# Crossing_v1_0.net
KiCad netlist of a schematic drawn in EAGLE
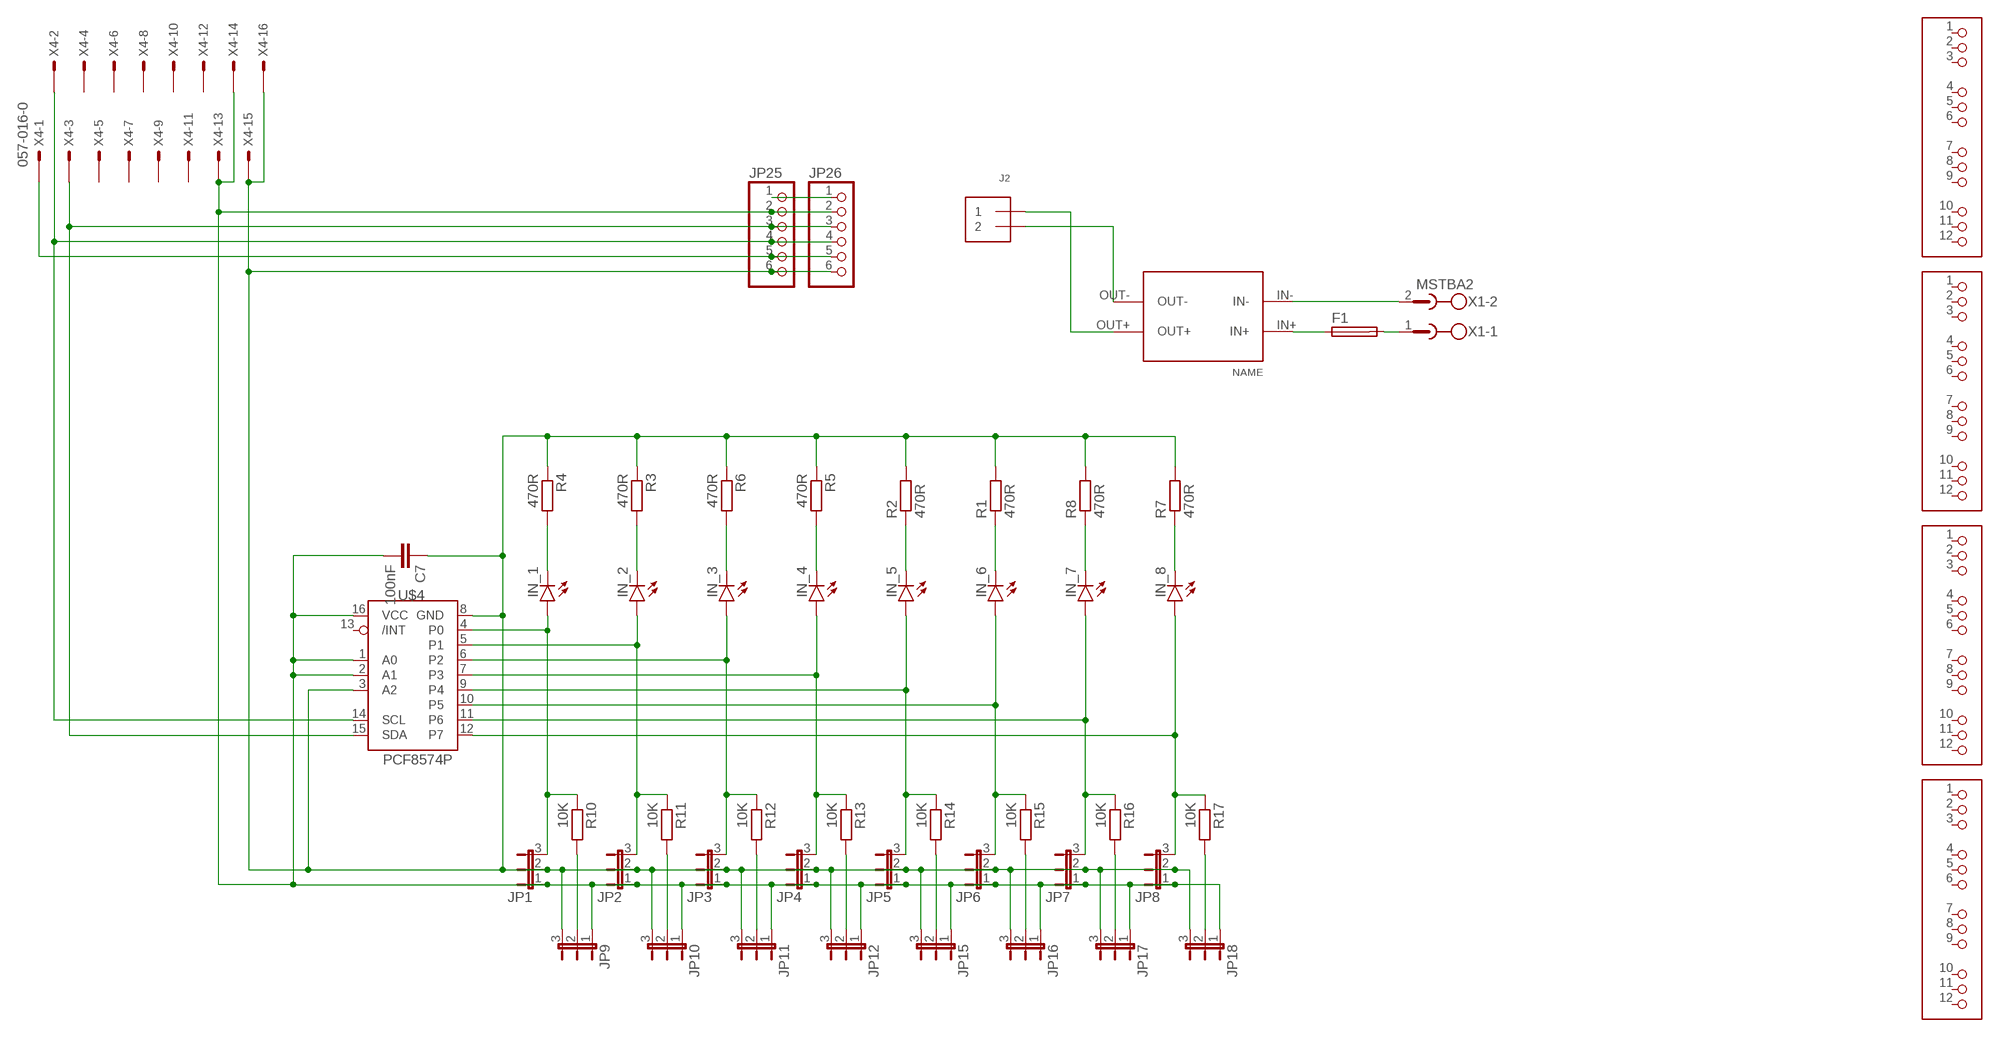
[diagram p0: schematic, sheet 1]

(export (version "E")
  (design (tool "Eeschema 10.0.6"))
  (components
    (comp (ref "C7")
      (value "100nF")
      (footprint "eagle-import:C025-024X044")
      (libsource (lib "eagle-import") (part "C-EU025-024X044"))
    )
    (comp (ref "F1")
      (value "SH25")
      (footprint "eagle-import:SH25")
      (fields (field (name "MF") "SCHURTER") (field (name "MPN") "0031.8211"))
      (libsource (lib "eagle-import") (part "SH25"))
    )
    (comp (ref "IN_1")
      (value "LED3MM")
      (footprint "eagle-import:LED3MM")
      (libsource (lib "eagle-import") (part "LED3MM"))
    )
    (comp (ref "IN_2")
      (value "LED3MM")
      (footprint "eagle-import:LED3MM")
      (libsource (lib "eagle-import") (part "LED3MM"))
    )
    (comp (ref "IN_3")
      (value "LED3MM")
      (footprint "eagle-import:LED3MM")
      (libsource (lib "eagle-import") (part "LED3MM"))
    )
    (comp (ref "IN_4")
      (value "LED3MM")
      (footprint "eagle-import:LED3MM")
      (libsource (lib "eagle-import") (part "LED3MM"))
    )
    (comp (ref "IN_5")
      (value "LED3MM")
      (footprint "eagle-import:LED3MM")
      (libsource (lib "eagle-import") (part "LED3MM"))
    )
    (comp (ref "IN_6")
      (value "LED3MM")
      (footprint "eagle-import:LED3MM")
      (libsource (lib "eagle-import") (part "LED3MM"))
    )
    (comp (ref "IN_7")
      (value "LED3MM")
      (footprint "eagle-import:LED3MM")
      (libsource (lib "eagle-import") (part "LED3MM"))
    )
    (comp (ref "IN_8")
      (value "LED3MM")
      (footprint "eagle-import:LED3MM")
      (libsource (lib "eagle-import") (part "LED3MM"))
    )
    (comp (ref "J2")
      (value "TERMBLOCK_1X2")
      (footprint "eagle-import:TERMBLOCK_1X2-3.5MM")
      (libsource (lib "eagle-import") (part "TERMBLOCK_1X2"))
    )
    (comp (ref "JP1")
      (value "JP2E")
      (footprint "eagle-import:JP2")
      (libsource (lib "eagle-import") (part "JP2E"))
    )
    (comp (ref "JP2")
      (value "JP2E")
      (footprint "eagle-import:JP2")
      (libsource (lib "eagle-import") (part "JP2E"))
    )
    (comp (ref "JP3")
      (value "JP2E")
      (footprint "eagle-import:JP2")
      (libsource (lib "eagle-import") (part "JP2E"))
    )
    (comp (ref "JP4")
      (value "JP2E")
      (footprint "eagle-import:JP2")
      (libsource (lib "eagle-import") (part "JP2E"))
    )
    (comp (ref "JP5")
      (value "JP2E")
      (footprint "eagle-import:JP2")
      (libsource (lib "eagle-import") (part "JP2E"))
    )
    (comp (ref "JP6")
      (value "JP2E")
      (footprint "eagle-import:JP2")
      (libsource (lib "eagle-import") (part "JP2E"))
    )
    (comp (ref "JP7")
      (value "JP2E")
      (footprint "eagle-import:JP2")
      (libsource (lib "eagle-import") (part "JP2E"))
    )
    (comp (ref "JP8")
      (value "JP2E")
      (footprint "eagle-import:JP2")
      (libsource (lib "eagle-import") (part "JP2E"))
    )
    (comp (ref "JP9")
      (value "JP2E")
      (footprint "eagle-import:JP2")
      (libsource (lib "eagle-import") (part "JP2E"))
    )
    (comp (ref "JP10")
      (value "JP2E")
      (footprint "eagle-import:JP2")
      (libsource (lib "eagle-import") (part "JP2E"))
    )
    (comp (ref "JP11")
      (value "JP2E")
      (footprint "eagle-import:JP2")
      (libsource (lib "eagle-import") (part "JP2E"))
    )
    (comp (ref "JP12")
      (value "JP2E")
      (footprint "eagle-import:JP2")
      (libsource (lib "eagle-import") (part "JP2E"))
    )
    (comp (ref "JP15")
      (value "JP2E")
      (footprint "eagle-import:JP2")
      (libsource (lib "eagle-import") (part "JP2E"))
    )
    (comp (ref "JP16")
      (value "JP2E")
      (footprint "eagle-import:JP2")
      (libsource (lib "eagle-import") (part "JP2E"))
    )
    (comp (ref "JP17")
      (value "JP2E")
      (footprint "eagle-import:JP2")
      (libsource (lib "eagle-import") (part "JP2E"))
    )
    (comp (ref "JP18")
      (value "JP2E")
      (footprint "eagle-import:JP2")
      (libsource (lib "eagle-import") (part "JP2E"))
    )
    (comp (ref "JP25")
      (value "PINHD-1X6CB")
      (footprint "eagle-import:1X06-CLEANBIG")
      (libsource (lib "eagle-import") (part "PINHD-1X6CB"))
    )
    (comp (ref "JP26")
      (value "PINHD-1X6CB")
      (footprint "eagle-import:1X06-CLEANBIG")
      (libsource (lib "eagle-import") (part "PINHD-1X6CB"))
    )
    (comp (ref "JP27")
      (value "HEADER-3X04")
      (footprint "eagle-import:3X04")
      (libsource (lib "eagle-import") (part "HEADER-3X04"))
    )
    (comp (ref "JP28")
      (value "HEADER-3X04")
      (footprint "eagle-import:3X04")
      (libsource (lib "eagle-import") (part "HEADER-3X04"))
    )
    (comp (ref "JP29")
      (value "HEADER-3X04")
      (footprint "eagle-import:3X04")
      (libsource (lib "eagle-import") (part "HEADER-3X04"))
    )
    (comp (ref "JP30")
      (value "HEADER-3X04")
      (footprint "eagle-import:3X04")
      (libsource (lib "eagle-import") (part "HEADER-3X04"))
    )
    (comp (ref "R1")
      (value "470R")
      (footprint "eagle-import:0309_10")
      (libsource (lib "eagle-import") (part "R-EU_0309/10"))
    )
    (comp (ref "R2")
      (value "470R")
      (footprint "eagle-import:0309_10")
      (libsource (lib "eagle-import") (part "R-EU_0309/10"))
    )
    (comp (ref "R3")
      (value "470R")
      (footprint "eagle-import:0309_10")
      (libsource (lib "eagle-import") (part "R-EU_0309/10"))
    )
    (comp (ref "R4")
      (value "470R")
      (footprint "eagle-import:0309_10")
      (libsource (lib "eagle-import") (part "R-EU_0309/10"))
    )
    (comp (ref "R5")
      (value "470R")
      (footprint "eagle-import:0309_10")
      (libsource (lib "eagle-import") (part "R-EU_0309/10"))
    )
    (comp (ref "R6")
      (value "470R")
      (footprint "eagle-import:0309_10")
      (libsource (lib "eagle-import") (part "R-EU_0309/10"))
    )
    (comp (ref "R7")
      (value "470R")
      (footprint "eagle-import:0309_10")
      (libsource (lib "eagle-import") (part "R-EU_0309/10"))
    )
    (comp (ref "R8")
      (value "470R")
      (footprint "eagle-import:0309_10")
      (libsource (lib "eagle-import") (part "R-EU_0309/10"))
    )
    (comp (ref "R10")
      (value "10K")
      (footprint "eagle-import:0309_10")
      (libsource (lib "eagle-import") (part "R-EU_0309/10"))
    )
    (comp (ref "R11")
      (value "10K")
      (footprint "eagle-import:0309_10")
      (libsource (lib "eagle-import") (part "R-EU_0309/10"))
    )
    (comp (ref "R12")
      (value "10K")
      (footprint "eagle-import:0309_10")
      (libsource (lib "eagle-import") (part "R-EU_0309/10"))
    )
    (comp (ref "R13")
      (value "10K")
      (footprint "eagle-import:0309_10")
      (libsource (lib "eagle-import") (part "R-EU_0309/10"))
    )
    (comp (ref "R14")
      (value "10K")
      (footprint "eagle-import:0309_10")
      (libsource (lib "eagle-import") (part "R-EU_0309/10"))
    )
    (comp (ref "R15")
      (value "10K")
      (footprint "eagle-import:0309_10")
      (libsource (lib "eagle-import") (part "R-EU_0309/10"))
    )
    (comp (ref "R16")
      (value "10K")
      (footprint "eagle-import:0309_10")
      (libsource (lib "eagle-import") (part "R-EU_0309/10"))
    )
    (comp (ref "R17")
      (value "10K")
      (footprint "eagle-import:0309_10")
      (libsource (lib "eagle-import") (part "R-EU_0309/10"))
    )
    (comp (ref "U$2")
      (value "CP8-ADJ")
      (footprint "eagle-import:CP8-ADJ")
      (libsource (lib "eagle-import") (part "CP8-ADJ"))
    )
    (comp (ref "U$4")
      (value "PCF8574P")
      (footprint "eagle-import:DIL16")
      (libsource (lib "eagle-import") (part "PCF8574P"))
    )
    (comp (ref "X1")
      (value "MSTBA2")
      (footprint "eagle-import:MSTBA2")
      (fields (field (name "MF") "FARNELL") (field (name "MPN") "1757242"))
      (libsource (lib "eagle-import") (part "MSTBA2"))
    )
    (comp (ref "X4")
      (value "057-016-0")
      (footprint "eagle-import:057-016-0")
      (libsource (lib "eagle-import") (part "057-016-0"))
    )
  )
  (nets
    (net (code "1") (name "Net-(F1-Pad1)") (class "Default")
      (node (ref "F1") (pin "1") (pinfunction "1_1") (pintype "passive"))
      (node (ref "U$2") (pin "IN+") (pinfunction "IN+_IN+") (pintype "passive"))
    )
    (net (code "2") (name "Net-(F1-Pad2)") (class "Default")
      (node (ref "F1") (pin "2") (pinfunction "2_2") (pintype "passive"))
      (node (ref "X1") (pin "1") (pinfunction "1_1") (pintype "passive"))
    )
    (net (code "3") (name "Net-(IN_1-C)") (class "Default")
      (node (ref "IN_1") (pin "K") (pinfunction "C_K") (pintype "passive"))
      (node (ref "R4") (pin "2") (pinfunction "2_2") (pintype "passive"))
    )
    (net (code "4") (name "Net-(IN_2-C)") (class "Default")
      (node (ref "IN_2") (pin "K") (pinfunction "C_K") (pintype "passive"))
      (node (ref "R3") (pin "2") (pinfunction "2_2") (pintype "passive"))
    )
    (net (code "5") (name "Net-(IN_3-C)") (class "Default")
      (node (ref "IN_3") (pin "K") (pinfunction "C_K") (pintype "passive"))
      (node (ref "R6") (pin "2") (pinfunction "2_2") (pintype "passive"))
    )
    (net (code "6") (name "Net-(IN_4-C)") (class "Default")
      (node (ref "IN_4") (pin "K") (pinfunction "C_K") (pintype "passive"))
      (node (ref "R5") (pin "2") (pinfunction "2_2") (pintype "passive"))
    )
    (net (code "7") (name "Net-(IN_5-C)") (class "Default")
      (node (ref "IN_5") (pin "K") (pinfunction "C_K") (pintype "passive"))
      (node (ref "R2") (pin "1") (pinfunction "1_1") (pintype "passive"))
    )
    (net (code "8") (name "Net-(IN_6-C)") (class "Default")
      (node (ref "IN_6") (pin "K") (pinfunction "C_K") (pintype "passive"))
      (node (ref "R1") (pin "1") (pinfunction "1_1") (pintype "passive"))
    )
    (net (code "9") (name "Net-(IN_7-C)") (class "Default")
      (node (ref "IN_7") (pin "K") (pinfunction "C_K") (pintype "passive"))
      (node (ref "R8") (pin "1") (pinfunction "1_1") (pintype "passive"))
    )
    (net (code "10") (name "Net-(IN_8-C)") (class "Default")
      (node (ref "IN_8") (pin "K") (pinfunction "C_K") (pintype "passive"))
      (node (ref "R7") (pin "1") (pinfunction "1_1") (pintype "passive"))
    )
    (net (code "11") (name "Net-(J2-Pad1)") (class "Default")
      (node (ref "J2") (pin "1") (pinfunction "1_1") (pintype "passive"))
      (node (ref "U$2") (pin "OUT+") (pinfunction "OUT+_OUT+") (pintype "passive"))
    )
    (net (code "12") (name "Net-(J2-Pad2)") (class "Default")
      (node (ref "J2") (pin "2") (pinfunction "2_2") (pintype "passive"))
      (node (ref "U$2") (pin "OUT-") (pinfunction "OUT-_OUT-") (pintype "passive"))
    )
    (net (code "13") (name "Net-(JP9-Pad2)") (class "Default")
      (node (ref "JP9") (pin "2") (pinfunction "2_2") (pintype "passive"))
      (node (ref "R10") (pin "2") (pinfunction "2_2") (pintype "passive"))
    )
    (net (code "14") (name "Net-(JP10-Pad2)") (class "Default")
      (node (ref "JP10") (pin "2") (pinfunction "2_2") (pintype "passive"))
      (node (ref "R11") (pin "2") (pinfunction "2_2") (pintype "passive"))
    )
    (net (code "15") (name "Net-(JP11-Pad2)") (class "Default")
      (node (ref "JP11") (pin "2") (pinfunction "2_2") (pintype "passive"))
      (node (ref "R12") (pin "2") (pinfunction "2_2") (pintype "passive"))
    )
    (net (code "16") (name "Net-(JP12-Pad2)") (class "Default")
      (node (ref "JP12") (pin "2") (pinfunction "2_2") (pintype "passive"))
      (node (ref "R13") (pin "2") (pinfunction "2_2") (pintype "passive"))
    )
    (net (code "17") (name "Net-(JP15-Pad2)") (class "Default")
      (node (ref "JP15") (pin "2") (pinfunction "2_2") (pintype "passive"))
      (node (ref "R14") (pin "2") (pinfunction "2_2") (pintype "passive"))
    )
    (net (code "18") (name "Net-(JP16-Pad2)") (class "Default")
      (node (ref "JP16") (pin "2") (pinfunction "2_2") (pintype "passive"))
      (node (ref "R15") (pin "2") (pinfunction "2_2") (pintype "passive"))
    )
    (net (code "19") (name "Net-(JP17-Pad2)") (class "Default")
      (node (ref "JP17") (pin "2") (pinfunction "2_2") (pintype "passive"))
      (node (ref "R16") (pin "2") (pinfunction "2_2") (pintype "passive"))
    )
    (net (code "20") (name "Net-(JP18-Pad2)") (class "Default")
      (node (ref "JP18") (pin "2") (pinfunction "2_2") (pintype "passive"))
      (node (ref "R17") (pin "2") (pinfunction "2_2") (pintype "passive"))
    )
    (net (code "21") (name "Net-(JP25-Pad1)") (class "Default")
      (node (ref "JP25") (pin "1") (pinfunction "1_1") (pintype "passive"))
      (node (ref "JP26") (pin "1") (pinfunction "1_1") (pintype "passive"))
    )
    (net (code "22") (name "Net-(U$4-A0)") (class "Default")
      (node (ref "C7") (pin "2") (pinfunction "2_2") (pintype "passive"))
      (node (ref "JP1") (pin "1") (pinfunction "1_1") (pintype "passive"))
      (node (ref "JP10") (pin "1") (pinfunction "1_1") (pintype "passive"))
      (node (ref "JP11") (pin "1") (pinfunction "1_1") (pintype "passive"))
      (node (ref "JP12") (pin "1") (pinfunction "1_1") (pintype "passive"))
      (node (ref "JP15") (pin "1") (pinfunction "1_1") (pintype "passive"))
      (node (ref "JP16") (pin "1") (pinfunction "1_1") (pintype "passive"))
      (node (ref "JP17") (pin "1") (pinfunction "1_1") (pintype "passive"))
      (node (ref "JP18") (pin "1") (pinfunction "1_1") (pintype "passive"))
      (node (ref "JP2") (pin "1") (pinfunction "1_1") (pintype "passive"))
      (node (ref "JP25") (pin "2") (pinfunction "2_2") (pintype "passive"))
      (node (ref "JP26") (pin "2") (pinfunction "2_2") (pintype "passive"))
      (node (ref "JP3") (pin "1") (pinfunction "1_1") (pintype "passive"))
      (node (ref "JP4") (pin "1") (pinfunction "1_1") (pintype "passive"))
      (node (ref "JP5") (pin "1") (pinfunction "1_1") (pintype "passive"))
      (node (ref "JP6") (pin "1") (pinfunction "1_1") (pintype "passive"))
      (node (ref "JP7") (pin "1") (pinfunction "1_1") (pintype "passive"))
      (node (ref "JP8") (pin "1") (pinfunction "1_1") (pintype "passive"))
      (node (ref "JP9") (pin "1") (pinfunction "1_1") (pintype "passive"))
      (node (ref "U$4") (pin "1") (pinfunction "A0_1") (pintype "input"))
      (node (ref "U$4") (pin "16") (pinfunction "VCC_16") (pintype "power_in"))
      (node (ref "U$4") (pin "2") (pinfunction "A1_2") (pintype "input"))
      (node (ref "X4") (pin "13") (pinfunction "S_13") (pintype "passive"))
      (node (ref "X4") (pin "14") (pinfunction "S_14") (pintype "passive"))
    )
    (net (code "23") (name "Net-(U$4-A2)") (class "Default")
      (node (ref "C7") (pin "1") (pinfunction "1_1") (pintype "passive"))
      (node (ref "JP1") (pin "2") (pinfunction "2_2") (pintype "passive"))
      (node (ref "JP10") (pin "3") (pinfunction "3_3") (pintype "passive"))
      (node (ref "JP11") (pin "3") (pinfunction "3_3") (pintype "passive"))
      (node (ref "JP12") (pin "3") (pinfunction "3_3") (pintype "passive"))
      (node (ref "JP15") (pin "3") (pinfunction "3_3") (pintype "passive"))
      (node (ref "JP16") (pin "3") (pinfunction "3_3") (pintype "passive"))
      (node (ref "JP17") (pin "3") (pinfunction "3_3") (pintype "passive"))
      (node (ref "JP18") (pin "3") (pinfunction "3_3") (pintype "passive"))
      (node (ref "JP2") (pin "2") (pinfunction "2_2") (pintype "passive"))
      (node (ref "JP25") (pin "6") (pinfunction "6_6") (pintype "passive"))
      (node (ref "JP26") (pin "6") (pinfunction "6_6") (pintype "passive"))
      (node (ref "JP3") (pin "2") (pinfunction "2_2") (pintype "passive"))
      (node (ref "JP4") (pin "2") (pinfunction "2_2") (pintype "passive"))
      (node (ref "JP5") (pin "2") (pinfunction "2_2") (pintype "passive"))
      (node (ref "JP6") (pin "2") (pinfunction "2_2") (pintype "passive"))
      (node (ref "JP7") (pin "2") (pinfunction "2_2") (pintype "passive"))
      (node (ref "JP8") (pin "2") (pinfunction "2_2") (pintype "passive"))
      (node (ref "JP9") (pin "3") (pinfunction "3_3") (pintype "passive"))
      (node (ref "R1") (pin "2") (pinfunction "2_2") (pintype "passive"))
      (node (ref "R2") (pin "2") (pinfunction "2_2") (pintype "passive"))
      (node (ref "R3") (pin "1") (pinfunction "1_1") (pintype "passive"))
      (node (ref "R4") (pin "1") (pinfunction "1_1") (pintype "passive"))
      (node (ref "R5") (pin "1") (pinfunction "1_1") (pintype "passive"))
      (node (ref "R6") (pin "1") (pinfunction "1_1") (pintype "passive"))
      (node (ref "R7") (pin "2") (pinfunction "2_2") (pintype "passive"))
      (node (ref "R8") (pin "2") (pinfunction "2_2") (pintype "passive"))
      (node (ref "U$4") (pin "3") (pinfunction "A2_3") (pintype "input"))
      (node (ref "U$4") (pin "8") (pinfunction "GND_8") (pintype "power_in"))
      (node (ref "X4") (pin "15") (pinfunction "S_15") (pintype "passive"))
      (node (ref "X4") (pin "16") (pinfunction "S_16") (pintype "passive"))
    )
    (net (code "24") (name "Net-(U$4-P0)") (class "Default")
      (node (ref "IN_1") (pin "A") (pinfunction "A_A") (pintype "passive"))
      (node (ref "JP1") (pin "3") (pinfunction "3_3") (pintype "passive"))
      (node (ref "R10") (pin "1") (pinfunction "1_1") (pintype "passive"))
      (node (ref "U$4") (pin "4") (pinfunction "P0_4") (pintype "bidirectional"))
    )
    (net (code "25") (name "Net-(U$4-P1)") (class "Default")
      (node (ref "IN_2") (pin "A") (pinfunction "A_A") (pintype "passive"))
      (node (ref "JP2") (pin "3") (pinfunction "3_3") (pintype "passive"))
      (node (ref "R11") (pin "1") (pinfunction "1_1") (pintype "passive"))
      (node (ref "U$4") (pin "5") (pinfunction "P1_5") (pintype "bidirectional"))
    )
    (net (code "26") (name "Net-(U$4-P2)") (class "Default")
      (node (ref "IN_3") (pin "A") (pinfunction "A_A") (pintype "passive"))
      (node (ref "JP3") (pin "3") (pinfunction "3_3") (pintype "passive"))
      (node (ref "R12") (pin "1") (pinfunction "1_1") (pintype "passive"))
      (node (ref "U$4") (pin "6") (pinfunction "P2_6") (pintype "bidirectional"))
    )
    (net (code "27") (name "Net-(U$4-P3)") (class "Default")
      (node (ref "IN_4") (pin "A") (pinfunction "A_A") (pintype "passive"))
      (node (ref "JP4") (pin "3") (pinfunction "3_3") (pintype "passive"))
      (node (ref "R13") (pin "1") (pinfunction "1_1") (pintype "passive"))
      (node (ref "U$4") (pin "7") (pinfunction "P3_7") (pintype "bidirectional"))
    )
    (net (code "28") (name "Net-(U$4-P4)") (class "Default")
      (node (ref "IN_5") (pin "A") (pinfunction "A_A") (pintype "passive"))
      (node (ref "JP5") (pin "3") (pinfunction "3_3") (pintype "passive"))
      (node (ref "R14") (pin "1") (pinfunction "1_1") (pintype "passive"))
      (node (ref "U$4") (pin "9") (pinfunction "P4_9") (pintype "bidirectional"))
    )
    (net (code "29") (name "Net-(U$4-P5)") (class "Default")
      (node (ref "IN_6") (pin "A") (pinfunction "A_A") (pintype "passive"))
      (node (ref "JP6") (pin "3") (pinfunction "3_3") (pintype "passive"))
      (node (ref "R15") (pin "1") (pinfunction "1_1") (pintype "passive"))
      (node (ref "U$4") (pin "10") (pinfunction "P5_10") (pintype "bidirectional"))
    )
    (net (code "30") (name "Net-(U$4-P6)") (class "Default")
      (node (ref "IN_7") (pin "A") (pinfunction "A_A") (pintype "passive"))
      (node (ref "JP7") (pin "3") (pinfunction "3_3") (pintype "passive"))
      (node (ref "R16") (pin "1") (pinfunction "1_1") (pintype "passive"))
      (node (ref "U$4") (pin "11") (pinfunction "P6_11") (pintype "bidirectional"))
    )
    (net (code "31") (name "Net-(U$4-P7)") (class "Default")
      (node (ref "IN_8") (pin "A") (pinfunction "A_A") (pintype "passive"))
      (node (ref "JP8") (pin "3") (pinfunction "3_3") (pintype "passive"))
      (node (ref "R17") (pin "1") (pinfunction "1_1") (pintype "passive"))
      (node (ref "U$4") (pin "12") (pinfunction "P7_12") (pintype "bidirectional"))
    )
    (net (code "32") (name "Net-(U$4-SCL)") (class "Default")
      (node (ref "JP25") (pin "4") (pinfunction "4_4") (pintype "passive"))
      (node (ref "JP26") (pin "4") (pinfunction "4_4") (pintype "passive"))
      (node (ref "U$4") (pin "14") (pinfunction "SCL_14") (pintype "input"))
      (node (ref "X4") (pin "2") (pinfunction "S_2") (pintype "passive"))
    )
    (net (code "33") (name "Net-(U$4-SDA)") (class "Default")
      (node (ref "JP25") (pin "3") (pinfunction "3_3") (pintype "passive"))
      (node (ref "JP26") (pin "3") (pinfunction "3_3") (pintype "passive"))
      (node (ref "U$4") (pin "15") (pinfunction "SDA_15") (pintype "bidirectional"))
      (node (ref "X4") (pin "3") (pinfunction "S_3") (pintype "passive"))
    )
    (net (code "34") (name "Net-(X1B-1)") (class "Default")
      (node (ref "U$2") (pin "IN-") (pinfunction "IN-_IN-") (pintype "passive"))
      (node (ref "X1") (pin "2") (pinfunction "1_2") (pintype "passive"))
    )
    (net (code "35") (name "Net-(X4A-S)") (class "Default")
      (node (ref "JP25") (pin "5") (pinfunction "5_5") (pintype "passive"))
      (node (ref "JP26") (pin "5") (pinfunction "5_5") (pintype "passive"))
      (node (ref "X4") (pin "1") (pinfunction "S_1") (pintype "passive"))
    )
    (net (code "36") (name "unconnected-(JP27-Pad1)") (class "Default")
      (node (ref "JP27") (pin "1") (pinfunction "1_1") (pintype "passive"))
    )
    (net (code "37") (name "unconnected-(JP27-Pad2)") (class "Default")
      (node (ref "JP27") (pin "2") (pinfunction "2_2") (pintype "passive"))
    )
    (net (code "38") (name "unconnected-(JP27-Pad3)") (class "Default")
      (node (ref "JP27") (pin "3") (pinfunction "3_3") (pintype "passive"))
    )
    (net (code "39") (name "unconnected-(JP27-Pad4)") (class "Default")
      (node (ref "JP27") (pin "4") (pinfunction "4_4") (pintype "passive"))
    )
    (net (code "40") (name "unconnected-(JP27-Pad5)") (class "Default")
      (node (ref "JP27") (pin "5") (pinfunction "5_5") (pintype "passive"))
    )
    (net (code "41") (name "unconnected-(JP27-Pad6)") (class "Default")
      (node (ref "JP27") (pin "6") (pinfunction "6_6") (pintype "passive"))
    )
    (net (code "42") (name "unconnected-(JP27-Pad7)") (class "Default")
      (node (ref "JP27") (pin "7") (pinfunction "7_7") (pintype "passive"))
    )
    (net (code "43") (name "unconnected-(JP27-Pad8)") (class "Default")
      (node (ref "JP27") (pin "8") (pinfunction "8_8") (pintype "passive"))
    )
    (net (code "44") (name "unconnected-(JP27-Pad9)") (class "Default")
      (node (ref "JP27") (pin "9") (pinfunction "9_9") (pintype "passive"))
    )
    (net (code "45") (name "unconnected-(JP27-Pad10)") (class "Default")
      (node (ref "JP27") (pin "10") (pinfunction "10_10") (pintype "passive"))
    )
    (net (code "46") (name "unconnected-(JP27-Pad11)") (class "Default")
      (node (ref "JP27") (pin "11") (pinfunction "11_11") (pintype "passive"))
    )
    (net (code "47") (name "unconnected-(JP27-Pad12)") (class "Default")
      (node (ref "JP27") (pin "12") (pinfunction "12_12") (pintype "passive"))
    )
    (net (code "48") (name "unconnected-(JP28-Pad1)") (class "Default")
      (node (ref "JP28") (pin "1") (pinfunction "1_1") (pintype "passive"))
    )
    (net (code "49") (name "unconnected-(JP28-Pad2)") (class "Default")
      (node (ref "JP28") (pin "2") (pinfunction "2_2") (pintype "passive"))
    )
    (net (code "50") (name "unconnected-(JP28-Pad3)") (class "Default")
      (node (ref "JP28") (pin "3") (pinfunction "3_3") (pintype "passive"))
    )
    (net (code "51") (name "unconnected-(JP28-Pad4)") (class "Default")
      (node (ref "JP28") (pin "4") (pinfunction "4_4") (pintype "passive"))
    )
    (net (code "52") (name "unconnected-(JP28-Pad5)") (class "Default")
      (node (ref "JP28") (pin "5") (pinfunction "5_5") (pintype "passive"))
    )
    (net (code "53") (name "unconnected-(JP28-Pad6)") (class "Default")
      (node (ref "JP28") (pin "6") (pinfunction "6_6") (pintype "passive"))
    )
    (net (code "54") (name "unconnected-(JP28-Pad7)") (class "Default")
      (node (ref "JP28") (pin "7") (pinfunction "7_7") (pintype "passive"))
    )
    (net (code "55") (name "unconnected-(JP28-Pad8)") (class "Default")
      (node (ref "JP28") (pin "8") (pinfunction "8_8") (pintype "passive"))
    )
    (net (code "56") (name "unconnected-(JP28-Pad9)") (class "Default")
      (node (ref "JP28") (pin "9") (pinfunction "9_9") (pintype "passive"))
    )
    (net (code "57") (name "unconnected-(JP28-Pad10)") (class "Default")
      (node (ref "JP28") (pin "10") (pinfunction "10_10") (pintype "passive"))
    )
    (net (code "58") (name "unconnected-(JP28-Pad11)") (class "Default")
      (node (ref "JP28") (pin "11") (pinfunction "11_11") (pintype "passive"))
    )
    (net (code "59") (name "unconnected-(JP28-Pad12)") (class "Default")
      (node (ref "JP28") (pin "12") (pinfunction "12_12") (pintype "passive"))
    )
    (net (code "60") (name "unconnected-(JP29-Pad1)") (class "Default")
      (node (ref "JP29") (pin "1") (pinfunction "1_1") (pintype "passive"))
    )
    (net (code "61") (name "unconnected-(JP29-Pad2)") (class "Default")
      (node (ref "JP29") (pin "2") (pinfunction "2_2") (pintype "passive"))
    )
    (net (code "62") (name "unconnected-(JP29-Pad3)") (class "Default")
      (node (ref "JP29") (pin "3") (pinfunction "3_3") (pintype "passive"))
    )
    (net (code "63") (name "unconnected-(JP29-Pad4)") (class "Default")
      (node (ref "JP29") (pin "4") (pinfunction "4_4") (pintype "passive"))
    )
    (net (code "64") (name "unconnected-(JP29-Pad5)") (class "Default")
      (node (ref "JP29") (pin "5") (pinfunction "5_5") (pintype "passive"))
    )
    (net (code "65") (name "unconnected-(JP29-Pad6)") (class "Default")
      (node (ref "JP29") (pin "6") (pinfunction "6_6") (pintype "passive"))
    )
    (net (code "66") (name "unconnected-(JP29-Pad7)") (class "Default")
      (node (ref "JP29") (pin "7") (pinfunction "7_7") (pintype "passive"))
    )
    (net (code "67") (name "unconnected-(JP29-Pad8)") (class "Default")
      (node (ref "JP29") (pin "8") (pinfunction "8_8") (pintype "passive"))
    )
    (net (code "68") (name "unconnected-(JP29-Pad9)") (class "Default")
      (node (ref "JP29") (pin "9") (pinfunction "9_9") (pintype "passive"))
    )
    (net (code "69") (name "unconnected-(JP29-Pad10)") (class "Default")
      (node (ref "JP29") (pin "10") (pinfunction "10_10") (pintype "passive"))
    )
    (net (code "70") (name "unconnected-(JP29-Pad11)") (class "Default")
      (node (ref "JP29") (pin "11") (pinfunction "11_11") (pintype "passive"))
    )
    (net (code "71") (name "unconnected-(JP29-Pad12)") (class "Default")
      (node (ref "JP29") (pin "12") (pinfunction "12_12") (pintype "passive"))
    )
    (net (code "72") (name "unconnected-(JP30-Pad1)") (class "Default")
      (node (ref "JP30") (pin "1") (pinfunction "1_1") (pintype "passive"))
    )
    (net (code "73") (name "unconnected-(JP30-Pad2)") (class "Default")
      (node (ref "JP30") (pin "2") (pinfunction "2_2") (pintype "passive"))
    )
    (net (code "74") (name "unconnected-(JP30-Pad3)") (class "Default")
      (node (ref "JP30") (pin "3") (pinfunction "3_3") (pintype "passive"))
    )
    (net (code "75") (name "unconnected-(JP30-Pad4)") (class "Default")
      (node (ref "JP30") (pin "4") (pinfunction "4_4") (pintype "passive"))
    )
    (net (code "76") (name "unconnected-(JP30-Pad5)") (class "Default")
      (node (ref "JP30") (pin "5") (pinfunction "5_5") (pintype "passive"))
    )
    (net (code "77") (name "unconnected-(JP30-Pad6)") (class "Default")
      (node (ref "JP30") (pin "6") (pinfunction "6_6") (pintype "passive"))
    )
    (net (code "78") (name "unconnected-(JP30-Pad7)") (class "Default")
      (node (ref "JP30") (pin "7") (pinfunction "7_7") (pintype "passive"))
    )
    (net (code "79") (name "unconnected-(JP30-Pad8)") (class "Default")
      (node (ref "JP30") (pin "8") (pinfunction "8_8") (pintype "passive"))
    )
    (net (code "80") (name "unconnected-(JP30-Pad9)") (class "Default")
      (node (ref "JP30") (pin "9") (pinfunction "9_9") (pintype "passive"))
    )
    (net (code "81") (name "unconnected-(JP30-Pad10)") (class "Default")
      (node (ref "JP30") (pin "10") (pinfunction "10_10") (pintype "passive"))
    )
    (net (code "82") (name "unconnected-(JP30-Pad11)") (class "Default")
      (node (ref "JP30") (pin "11") (pinfunction "11_11") (pintype "passive"))
    )
    (net (code "83") (name "unconnected-(JP30-Pad12)") (class "Default")
      (node (ref "JP30") (pin "12") (pinfunction "12_12") (pintype "passive"))
    )
    (net (code "84") (name "unconnected-(U$4-{slash}INT-Pad13)") (class "Default")
      (node (ref "U$4") (pin "13") (pinfunction "/INT_13") (pintype "output"))
    )
    (net (code "85") (name "unconnected-(X4B-S-Pad10)") (class "Default")
      (node (ref "X4") (pin "10") (pinfunction "S_10") (pintype "passive"))
    )
    (net (code "86") (name "unconnected-(X4C-S-Pad11)") (class "Default")
      (node (ref "X4") (pin "11") (pinfunction "S_11") (pintype "passive"))
    )
    (net (code "87") (name "unconnected-(X4D-S-Pad12)") (class "Default")
      (node (ref "X4") (pin "12") (pinfunction "S_12") (pintype "passive"))
    )
    (net (code "88") (name "unconnected-(X4K-S-Pad4)") (class "Default")
      (node (ref "X4") (pin "4") (pinfunction "S_4") (pintype "passive"))
    )
    (net (code "89") (name "unconnected-(X4L-S-Pad5)") (class "Default")
      (node (ref "X4") (pin "5") (pinfunction "S_5") (pintype "passive"))
    )
    (net (code "90") (name "unconnected-(X4M-S-Pad6)") (class "Default")
      (node (ref "X4") (pin "6") (pinfunction "S_6") (pintype "passive"))
    )
    (net (code "91") (name "unconnected-(X4N-S-Pad7)") (class "Default")
      (node (ref "X4") (pin "7") (pinfunction "S_7") (pintype "passive"))
    )
    (net (code "92") (name "unconnected-(X4O-S-Pad8)") (class "Default")
      (node (ref "X4") (pin "8") (pinfunction "S_8") (pintype "passive"))
    )
    (net (code "93") (name "unconnected-(X4P-S-Pad9)") (class "Default")
      (node (ref "X4") (pin "9") (pinfunction "S_9") (pintype "passive"))
    )
  )
)
